# 02_-MCU.net
KiCad netlist of a schematic drawn in Altium Designer
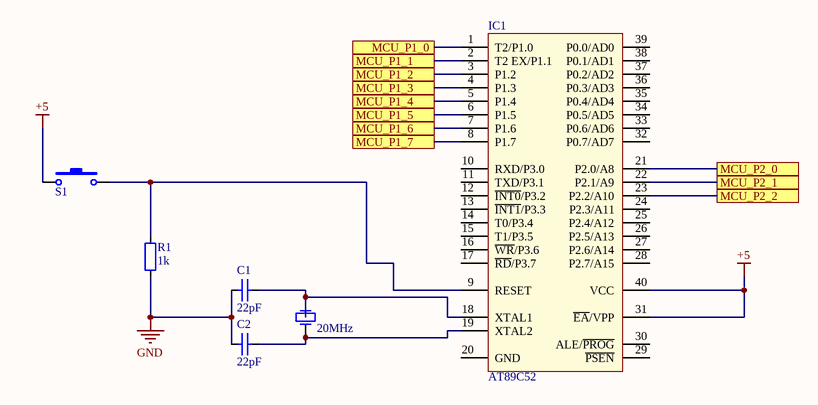
[diagram p0: [02]-MCU.SchDoc]

(export (version "E")
  (design (tool "Eeschema 10.0.6"))
  (components
    (comp (ref "C1")
      (value "22pF")
      (footprint "CAP_0805")
      (description "Capacitor")
      (fields (field (name "PUBLISHER") "Altium Limited"))
      (libsource (lib "My Library") (part "CapSMD"))
    )
    (comp (ref "C2")
      (value "22pF")
      (footprint "CAP_0805")
      (description "Capacitor")
      (fields (field (name "PUBLISHER") "Altium Limited"))
      (libsource (lib "My Library") (part "CapSMD"))
    )
    (comp (ref "IC1")
      (value "AT89C52")
      (footprint "DIP40/W0.6")
      (description "Atmel AT89C52, 8k Byte Flash Memory , 40 Pin")
      (libsource (lib "My Library") (part "AT89C52"))
    )
    (comp (ref "R1")
      (value "1k")
      (footprint "RES-SMD-0805")
      (description "Resistor - DIP")
      (libsource (lib "My Library") (part "Resistor - DIP"))
    )
    (comp (ref "S1")
      (value "SW-SMD")
      (footprint "SW-SMD")
      (description "Switch")
      (fields (field (name "PUBLISHER") "Altium Limited"))
      (libsource (lib "My Library") (part "SW-SMD"))
    )
    (comp (ref "Y1")
      (value "20MHz")
      (footprint "XTAL")
      (description "Crystal Oscillator")
      (fields (field (name "PUBLISHER") "Altium Limited"))
      (libsource (lib "My Library") (part "XTAL"))
    )
  )
  (nets
    (net (code "1") (name "+5") (class "Default")
      (node (ref "IC1") (pin "31") (pinfunction "~{EA}/VPP_31") (pintype "passive"))
      (node (ref "IC1") (pin "40") (pinfunction "VCC_40") (pintype "power_in"))
      (node (ref "S1") (pin "1") (pinfunction "1_1") (pintype "passive"))
    )
    (net (code "2") (name "/MCU_P1_0") (class "Default")
      (node (ref "IC1") (pin "1") (pinfunction "T2/P1.0_1") (pintype "passive"))
    )
    (net (code "3") (name "/MCU_P1_1") (class "Default")
      (node (ref "IC1") (pin "2") (pinfunction "T2_EX/P1.1_2") (pintype "passive"))
    )
    (net (code "4") (name "/MCU_P1_2") (class "Default")
      (node (ref "IC1") (pin "3") (pinfunction "P1.2_3") (pintype "passive"))
    )
    (net (code "5") (name "/MCU_P1_3") (class "Default")
      (node (ref "IC1") (pin "4") (pinfunction "P1.3_4") (pintype "passive"))
    )
    (net (code "6") (name "/MCU_P1_4") (class "Default")
      (node (ref "IC1") (pin "5") (pinfunction "P1.4_5") (pintype "passive"))
    )
    (net (code "7") (name "/MCU_P1_5") (class "Default")
      (node (ref "IC1") (pin "6") (pinfunction "P1.5_6") (pintype "passive"))
    )
    (net (code "8") (name "/MCU_P1_6") (class "Default")
      (node (ref "IC1") (pin "7") (pinfunction "P1.6_7") (pintype "passive"))
    )
    (net (code "9") (name "/MCU_P1_7") (class "Default")
      (node (ref "IC1") (pin "8") (pinfunction "P1.7_8") (pintype "passive"))
    )
    (net (code "10") (name "/MCU_P2_0") (class "Default")
      (node (ref "IC1") (pin "21") (pinfunction "P2.0/A8_21") (pintype "passive"))
    )
    (net (code "11") (name "/MCU_P2_1") (class "Default")
      (node (ref "IC1") (pin "22") (pinfunction "P2.1/A9_22") (pintype "passive"))
    )
    (net (code "12") (name "/MCU_P2_2") (class "Default")
      (node (ref "IC1") (pin "23") (pinfunction "P2.2/A10_23") (pintype "passive"))
    )
    (net (code "13") (name "GND") (class "Default")
      (node (ref "C1") (pin "1") (pinfunction "1_1") (pintype "passive"))
      (node (ref "C2") (pin "1") (pinfunction "1_1") (pintype "passive"))
      (node (ref "R1") (pin "1") (pinfunction "1_1") (pintype "passive"))
    )
    (net (code "14") (name "Net-(IC1-RESET)") (class "Default")
      (node (ref "IC1") (pin "9") (pinfunction "RESET_9") (pintype "passive"))
      (node (ref "R1") (pin "2") (pinfunction "2_2") (pintype "passive"))
      (node (ref "S1") (pin "2") (pinfunction "2_2") (pintype "passive"))
    )
    (net (code "15") (name "Net-(IC1-XTAL1)") (class "Default")
      (node (ref "C1") (pin "2") (pinfunction "2_2") (pintype "passive"))
      (node (ref "IC1") (pin "18") (pinfunction "XTAL1_18") (pintype "passive"))
      (node (ref "Y1") (pin "2") (pinfunction "OSC2_2") (pintype "passive"))
    )
    (net (code "16") (name "Net-(IC1-XTAL2)") (class "Default")
      (node (ref "C2") (pin "2") (pinfunction "2_2") (pintype "passive"))
      (node (ref "IC1") (pin "19") (pinfunction "XTAL2_19") (pintype "passive"))
      (node (ref "Y1") (pin "1") (pinfunction "OSC1_1") (pintype "passive"))
    )
    (net (code "17") (name "unconnected-(IC1-ALE{slash}~{PROG}-Pad30)") (class "Default")
      (node (ref "IC1") (pin "30") (pinfunction "ALE/~{PROG}_30") (pintype "passive"))
    )
    (net (code "18") (name "unconnected-(IC1-GND-Pad20)") (class "Default")
      (node (ref "IC1") (pin "20") (pinfunction "GND_20") (pintype "open_emitter"))
    )
    (net (code "19") (name "unconnected-(IC1-P0.0{slash}AD0-Pad39)") (class "Default")
      (node (ref "IC1") (pin "39") (pinfunction "P0.0/AD0_39") (pintype "passive"))
    )
    (net (code "20") (name "unconnected-(IC1-P0.1{slash}AD1-Pad38)") (class "Default")
      (node (ref "IC1") (pin "38") (pinfunction "P0.1/AD1_38") (pintype "passive"))
    )
    (net (code "21") (name "unconnected-(IC1-P0.2{slash}AD2-Pad37)") (class "Default")
      (node (ref "IC1") (pin "37") (pinfunction "P0.2/AD2_37") (pintype "passive"))
    )
    (net (code "22") (name "unconnected-(IC1-P0.3{slash}AD3-Pad36)") (class "Default")
      (node (ref "IC1") (pin "36") (pinfunction "P0.3/AD3_36") (pintype "passive"))
    )
    (net (code "23") (name "unconnected-(IC1-P0.4{slash}AD4-Pad35)") (class "Default")
      (node (ref "IC1") (pin "35") (pinfunction "P0.4/AD4_35") (pintype "passive"))
    )
    (net (code "24") (name "unconnected-(IC1-P0.5{slash}AD5-Pad34)") (class "Default")
      (node (ref "IC1") (pin "34") (pinfunction "P0.5/AD5_34") (pintype "passive"))
    )
    (net (code "25") (name "unconnected-(IC1-P0.6{slash}AD6-Pad33)") (class "Default")
      (node (ref "IC1") (pin "33") (pinfunction "P0.6/AD6_33") (pintype "passive"))
    )
    (net (code "26") (name "unconnected-(IC1-P0.7{slash}AD7-Pad32)") (class "Default")
      (node (ref "IC1") (pin "32") (pinfunction "P0.7/AD7_32") (pintype "passive"))
    )
    (net (code "27") (name "unconnected-(IC1-P2.3{slash}A11-Pad24)") (class "Default")
      (node (ref "IC1") (pin "24") (pinfunction "P2.3/A11_24") (pintype "passive"))
    )
    (net (code "28") (name "unconnected-(IC1-P2.4{slash}A12-Pad25)") (class "Default")
      (node (ref "IC1") (pin "25") (pinfunction "P2.4/A12_25") (pintype "passive"))
    )
    (net (code "29") (name "unconnected-(IC1-P2.5{slash}A13-Pad26)") (class "Default")
      (node (ref "IC1") (pin "26") (pinfunction "P2.5/A13_26") (pintype "passive"))
    )
    (net (code "30") (name "unconnected-(IC1-P2.6{slash}A14-Pad27)") (class "Default")
      (node (ref "IC1") (pin "27") (pinfunction "P2.6/A14_27") (pintype "passive"))
    )
    (net (code "31") (name "unconnected-(IC1-P2.7{slash}A15-Pad28)") (class "Default")
      (node (ref "IC1") (pin "28") (pinfunction "P2.7/A15_28") (pintype "passive"))
    )
    (net (code "32") (name "unconnected-(IC1-RXD{slash}P3.0-Pad10)") (class "Default")
      (node (ref "IC1") (pin "10") (pinfunction "RXD/P3.0_10") (pintype "passive"))
    )
    (net (code "33") (name "unconnected-(IC1-T0{slash}P3.4-Pad14)") (class "Default")
      (node (ref "IC1") (pin "14") (pinfunction "T0/P3.4_14") (pintype "passive"))
    )
    (net (code "34") (name "unconnected-(IC1-T1{slash}P3.5-Pad15)") (class "Default")
      (node (ref "IC1") (pin "15") (pinfunction "T1/P3.5_15") (pintype "passive"))
    )
    (net (code "35") (name "unconnected-(IC1-TXD{slash}P3.1-Pad11)") (class "Default")
      (node (ref "IC1") (pin "11") (pinfunction "TXD/P3.1_11") (pintype "passive"))
    )
    (net (code "36") (name "unconnected-(IC1-~{INT0}{slash}P3.2-Pad12)") (class "Default")
      (node (ref "IC1") (pin "12") (pinfunction "~{INT0}/P3.2_12") (pintype "passive"))
    )
    (net (code "37") (name "unconnected-(IC1-~{INT1}{slash}P3.3-Pad13)") (class "Default")
      (node (ref "IC1") (pin "13") (pinfunction "~{INT1}/P3.3_13") (pintype "passive"))
    )
    (net (code "38") (name "unconnected-(IC1-~{PSEN}-Pad29)") (class "Default")
      (node (ref "IC1") (pin "29") (pinfunction "~{PSEN}_29") (pintype "passive"))
    )
    (net (code "39") (name "unconnected-(IC1-~{RD}{slash}P3.7-Pad17)") (class "Default")
      (node (ref "IC1") (pin "17") (pinfunction "~{RD}/P3.7_17") (pintype "passive"))
    )
    (net (code "40") (name "unconnected-(IC1-~{WR}{slash}P3.6-Pad16)") (class "Default")
      (node (ref "IC1") (pin "16") (pinfunction "~{WR}/P3.6_16") (pintype "passive"))
    )
  )
)
